# Thrusters_V2_0.net
KiCad netlist of a schematic drawn in Altium Designer
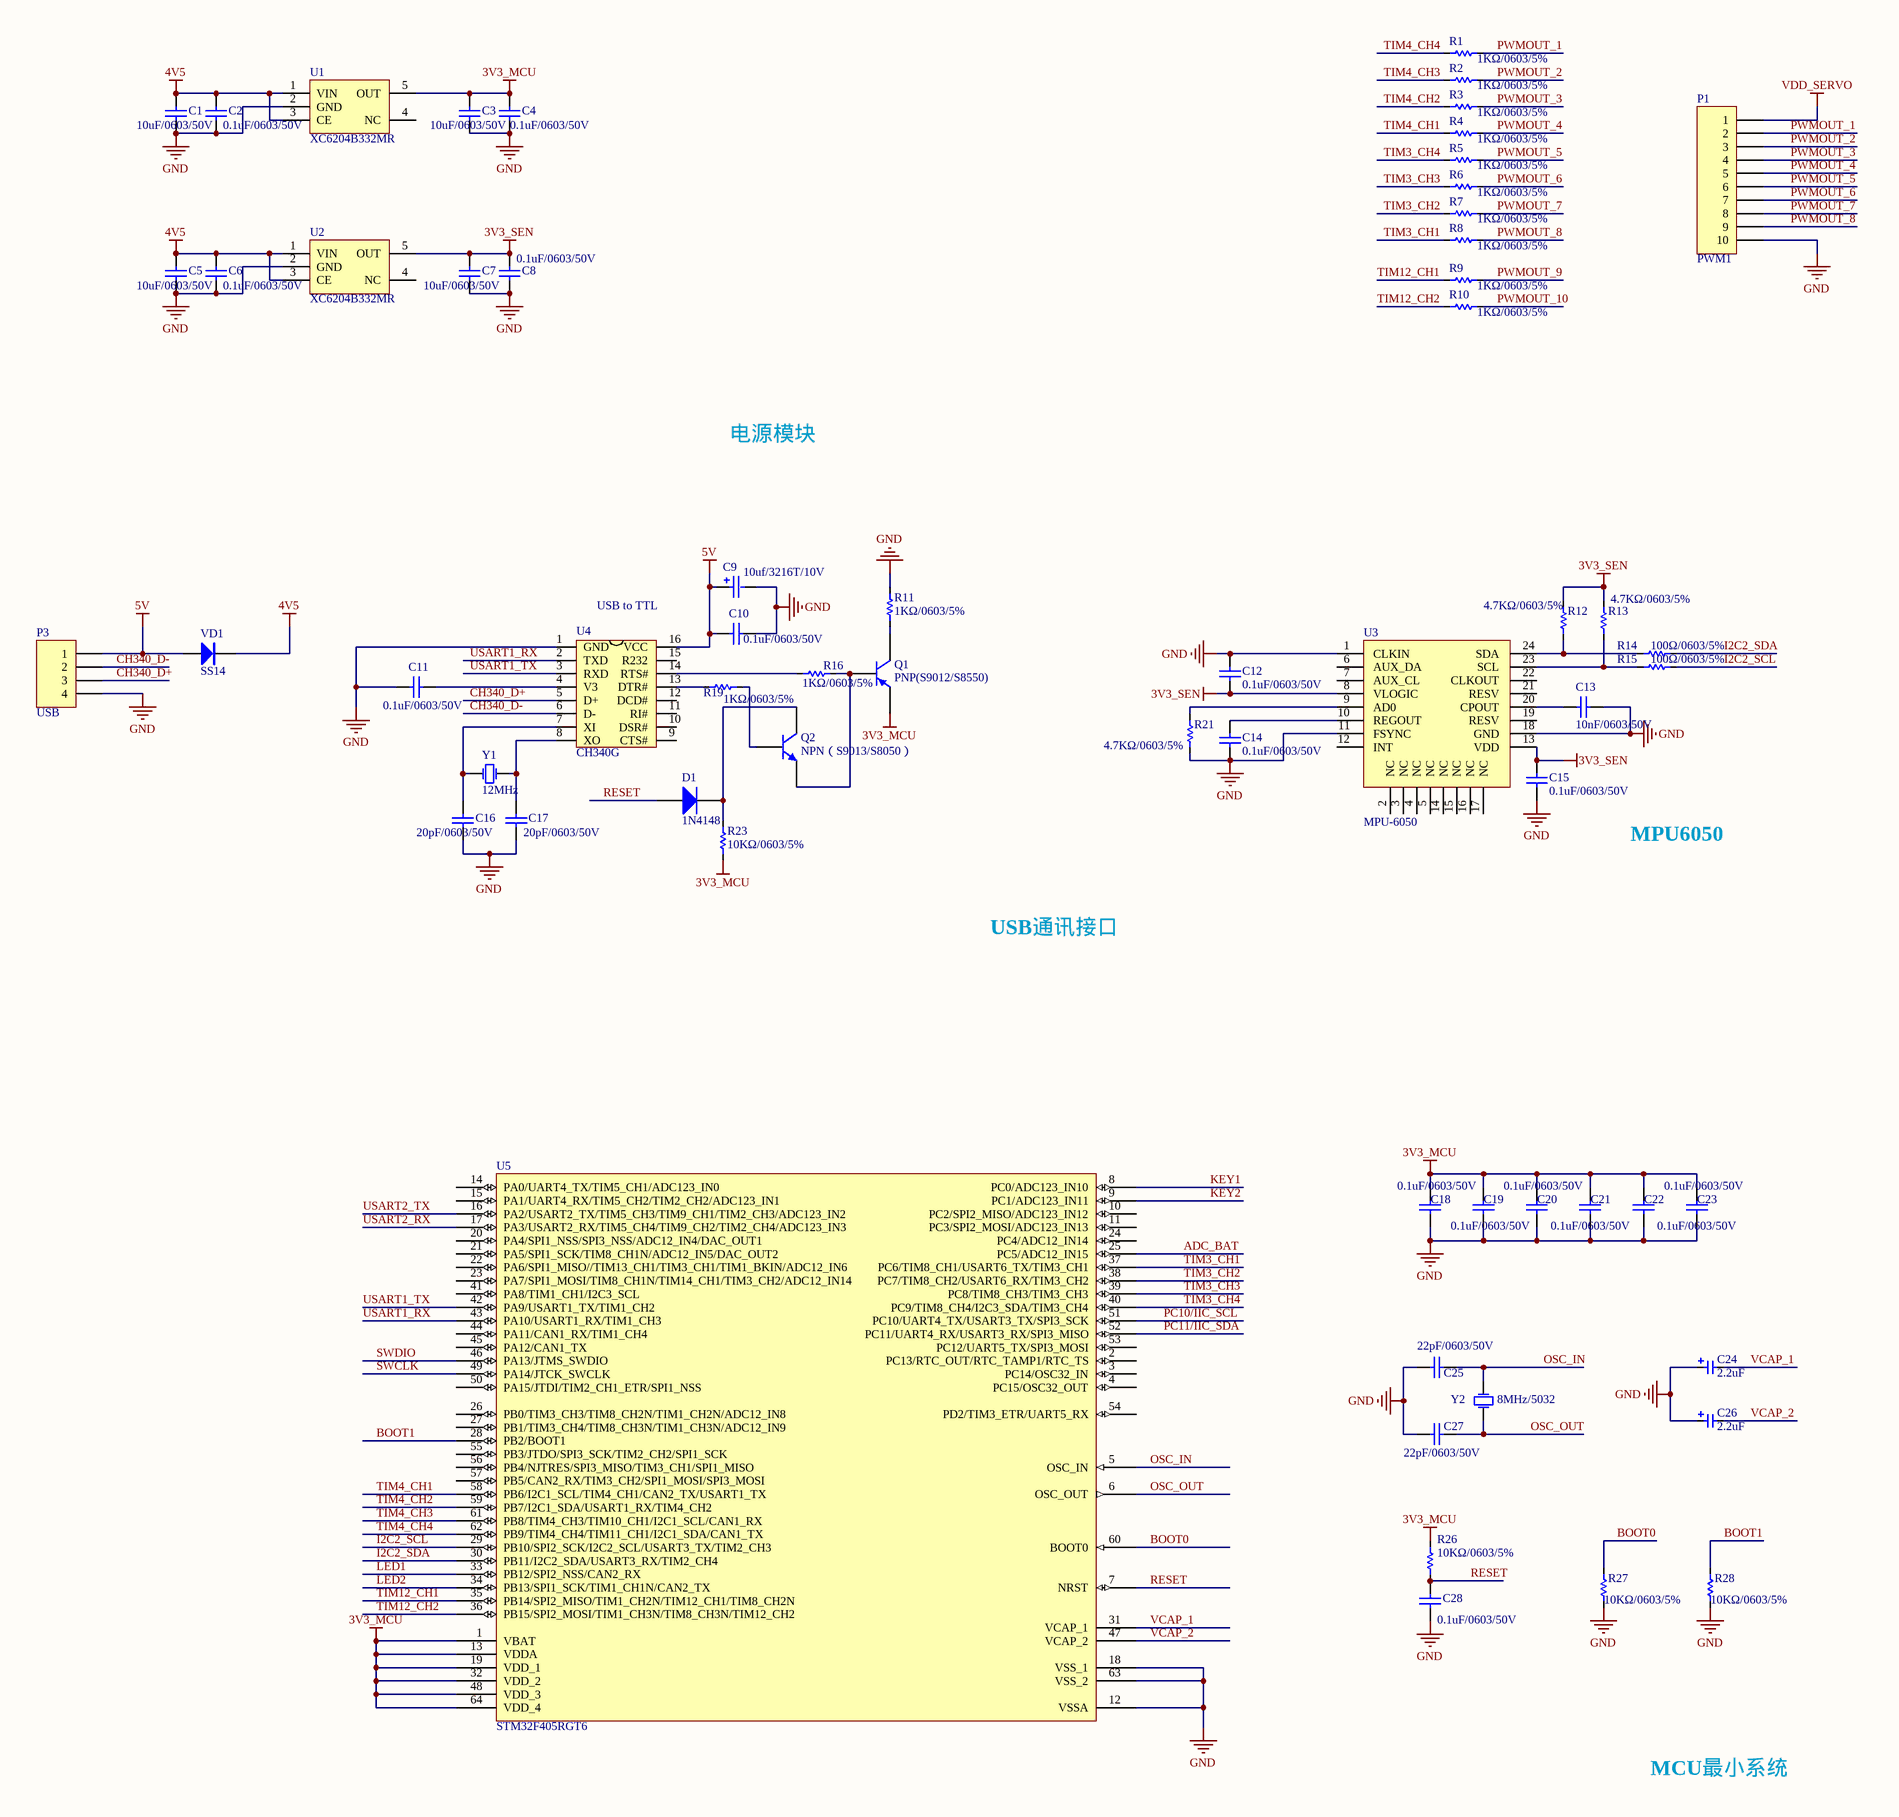
[diagram p0: Thrusters_V2.0.SchDoc, left]
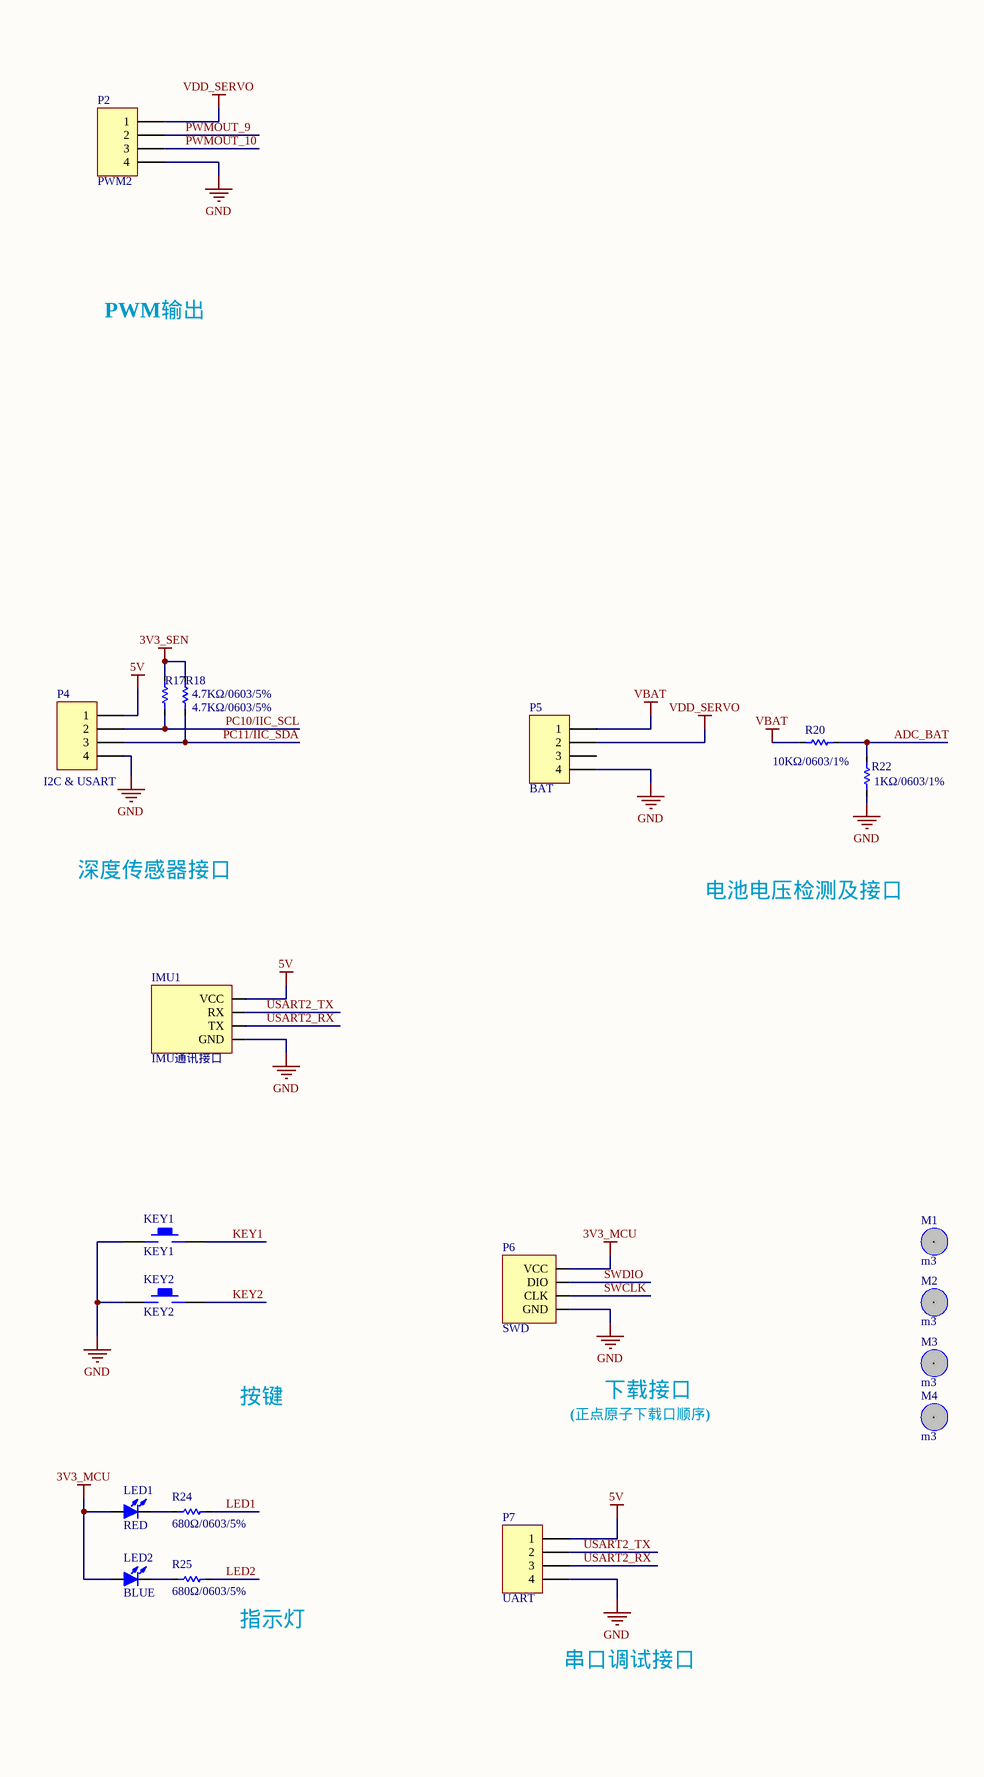
[diagram p1: Thrusters_V2.0.SchDoc, right]

(export (version "E")
  (design (tool "Eeschema 10.0.6"))
  (components
    (comp (ref "C1")
      (value "10uF/0603/50V")
      (footprint "C0805-JLC")
      (description "CAP 0805 0603 0402")
      (libsource (lib "wgcoSchlib") (part "CAP_0805/0603/0402"))
    )
    (comp (ref "C2")
      (value "0.1uF/0603/50V")
      (footprint "C0603-JLC")
      (description "CAP 0805 0603 0402")
      (libsource (lib "wgcoSchlib") (part "CAP_0805/0603/0402"))
    )
    (comp (ref "C3")
      (value "10uF/0603/50V")
      (footprint "C0805-JLC")
      (description "CAP 0805 0603 0402")
      (libsource (lib "wgcoSchlib") (part "CAP_0805/0603/0402"))
    )
    (comp (ref "C4")
      (value "0.1uF/0603/50V")
      (footprint "C0603-JLC")
      (description "CAP 0805 0603 0402")
      (libsource (lib "wgcoSchlib") (part "CAP_0805/0603/0402"))
    )
    (comp (ref "C5")
      (value "10uF/0603/50V")
      (footprint "C0805-JLC")
      (description "CAP 0805 0603 0402")
      (libsource (lib "wgcoSchlib") (part "CAP_0805/0603/0402"))
    )
    (comp (ref "C6")
      (value "0.1uF/0603/50V")
      (footprint "C0603-JLC")
      (description "CAP 0805 0603 0402")
      (libsource (lib "wgcoSchlib") (part "CAP_0805/0603/0402"))
    )
    (comp (ref "C7")
      (value "10uF/0603/50V")
      (footprint "C0805-JLC")
      (description "CAP 0805 0603 0402")
      (libsource (lib "wgcoSchlib") (part "CAP_0805/0603/0402"))
    )
    (comp (ref "C8")
      (value "0.1uF/0603/50V")
      (footprint "C0603-JLC")
      (description "CAP 0805 0603 0402")
      (libsource (lib "wgcoSchlib") (part "CAP_0805/0603/0402"))
    )
    (comp (ref "C9")
      (value "10uf/3216T/10V")
      (footprint "Cap Poll 1(3216T)")
      (description "Polarized Capacitor (Surface Mount)(钽电容)")
      (libsource (lib "wgcoSchlib") (part "Cap Poll"))
    )
    (comp (ref "C10")
      (value "0.1uF/0603/50V")
      (footprint "C0603-JLC")
      (description "CAP 0805 0603 0402")
      (libsource (lib "wgcoSchlib") (part "CAP_0805/0603/0402"))
    )
    (comp (ref "C11")
      (value "0.1uF/0603/50V")
      (footprint "C0603-JLC")
      (description "CAP 0805 0603 0402")
      (libsource (lib "wgcoSchlib") (part "CAP_0805/0603/0402"))
    )
    (comp (ref "C12")
      (value "0.1uF/0603/50V")
      (footprint "C0603-JLC")
      (description "CAP 0805 0603 0402")
      (libsource (lib "wgcoSchlib") (part "CAP_0805/0603/0402"))
    )
    (comp (ref "C13")
      (value "10nF/0603/50V")
      (footprint "C0603-JLC")
      (description "CAP 0805 0603 0402")
      (libsource (lib "wgcoSchlib") (part "CAP_0805/0603/0402"))
    )
    (comp (ref "C14")
      (value "0.1uF/0603/50V")
      (footprint "C0603-JLC")
      (description "CAP 0805 0603 0402")
      (libsource (lib "wgcoSchlib") (part "CAP_0805/0603/0402"))
    )
    (comp (ref "C15")
      (value "0.1uF/0603/50V")
      (footprint "C0603-JLC")
      (description "CAP 0805 0603 0402")
      (libsource (lib "wgcoSchlib") (part "CAP_0805/0603/0402"))
    )
    (comp (ref "C16")
      (value "20pF/0603/50V")
      (footprint "C0603-JLC")
      (description "CAP 0805 0603 0402")
      (libsource (lib "wgcoSchlib") (part "CAP_0805/0603/0402"))
    )
    (comp (ref "C17")
      (value "20pF/0603/50V")
      (footprint "C0603-JLC")
      (description "CAP 0805 0603 0402")
      (libsource (lib "wgcoSchlib") (part "CAP_0805/0603/0402"))
    )
    (comp (ref "C18")
      (value "0.1uF/0603/50V")
      (footprint "C0603-JLC")
      (description "CAP 0805 0603 0402")
      (libsource (lib "wgcoSchlib") (part "CAP_0805/0603/0402"))
    )
    (comp (ref "C19")
      (value "0.1uF/0603/50V")
      (footprint "C0603-JLC")
      (description "CAP 0805 0603 0402")
      (libsource (lib "wgcoSchlib") (part "CAP_0805/0603/0402"))
    )
    (comp (ref "C20")
      (value "0.1uF/0603/50V")
      (footprint "C0603-JLC")
      (description "CAP 0805 0603 0402")
      (libsource (lib "wgcoSchlib") (part "CAP_0805/0603/0402"))
    )
    (comp (ref "C21")
      (value "0.1uF/0603/50V")
      (footprint "C0603-JLC")
      (description "CAP 0805 0603 0402")
      (libsource (lib "wgcoSchlib") (part "CAP_0805/0603/0402"))
    )
    (comp (ref "C22")
      (value "0.1uF/0603/50V")
      (footprint "C0603-JLC")
      (description "CAP 0805 0603 0402")
      (libsource (lib "wgcoSchlib") (part "CAP_0805/0603/0402"))
    )
    (comp (ref "C23")
      (value "0.1uF/0603/50V")
      (footprint "C0603-JLC")
      (description "CAP 0805 0603 0402")
      (libsource (lib "wgcoSchlib") (part "CAP_0805/0603/0402"))
    )
    (comp (ref "C24")
      (value "2.2uF")
      (footprint "0603_C")
      (description "Polarized Capacitor (Surface Mount)(钽电容)")
      (fields (field (name "Comment") "Cap_Tan_0805"))
      (libsource (lib "wgcoSchlib") (part "Cap_Tan_0805"))
    )
    (comp (ref "C25")
      (value "22pF/0603/50V")
      (footprint "C0603-JLC")
      (description "CAP 0805 0603 0402")
      (libsource (lib "wgcoSchlib") (part "CAP_0805/0603/0402"))
    )
    (comp (ref "C26")
      (value "2.2uF")
      (footprint "0603_C")
      (description "Polarized Capacitor (Surface Mount)(钽电容)")
      (fields (field (name "Comment") "Cap_Tan_0805"))
      (libsource (lib "wgcoSchlib") (part "Cap_Tan_0805"))
    )
    (comp (ref "C27")
      (value "22pF/0603/50V")
      (footprint "C0603-JLC")
      (description "CAP 0805 0603 0402")
      (libsource (lib "wgcoSchlib") (part "CAP_0805/0603/0402"))
    )
    (comp (ref "C28")
      (value "0.1uF/0603/50V")
      (footprint "C0603-JLC")
      (description "CAP 0805 0603 0402")
      (libsource (lib "wgcoSchlib") (part "CAP_0805/0603/0402"))
    )
    (comp (ref "D1") (value "1N4148") (footprint "SOD-123F") (libsource (lib "wgcoSchlib") (part "D")))
    (comp (ref "IMU1")
      (value "IMU通讯接口")
      (footprint "ATK-IMU901")
      (description "正点原子ATK-IMU901模块接口")
      (libsource (lib "wgcoSchlib") (part "ATK-IMU901"))
    )
    (comp (ref "KEY1")
      (value "KEY1")
      (footprint "button-3x4x2mm 2 Pad")
      (description "按键")
      (libsource (lib "wgcoSchlib") (part "KEY"))
    )
    (comp (ref "KEY2")
      (value "KEY2")
      (footprint "button-3x4x2mm 2 Pad")
      (description "按键")
      (libsource (lib "wgcoSchlib") (part "KEY"))
    )
    (comp (ref "LED1")
      (value "RED")
      (footprint "LED0603-RED-JLC")
      (description "贴片LED")
      (fields (field (name "版权归属") "源创客"))
      (libsource (lib "wgcoSchlib") (part "LED-SMD"))
    )
    (comp (ref "LED2")
      (value "BLUE")
      (footprint "LED0603-RED-JLC")
      (description "贴片LED")
      (fields (field (name "版权归属") "源创客"))
      (libsource (lib "wgcoSchlib") (part "LED-SMD"))
    )
    (comp (ref "M1")
      (value "m3")
      (footprint "M3固定孔")
      (description "M3固定孔")
      (libsource (lib "wgcoSchlib") (part "M3固定孔"))
    )
    (comp (ref "M2")
      (value "m3")
      (footprint "M3固定孔")
      (description "M3固定孔")
      (libsource (lib "wgcoSchlib") (part "M3固定孔"))
    )
    (comp (ref "M3")
      (value "m3")
      (footprint "M3固定孔")
      (description "M3固定孔")
      (libsource (lib "wgcoSchlib") (part "M3固定孔"))
    )
    (comp (ref "M4")
      (value "m3")
      (footprint "M3固定孔")
      (description "M3固定孔")
      (libsource (lib "wgcoSchlib") (part "M3固定孔"))
    )
    (comp (ref "P1")
      (value "PWM1")
      (footprint "HEADER-GH1.25-10P")
      (description "Header, 8-Pin")
      (libsource (lib "wgcoSchlib") (part "HEADER10"))
    )
    (comp (ref "P2")
      (value "PWM2")
      (footprint "HEADER-GH1.25-4P")
      (description "Header, 4-Pin")
      (libsource (lib "wgcoSchlib") (part "HEADER4"))
    )
    (comp (ref "P3")
      (value "USB")
      (footprint "HEADER-GH1.25-4P")
      (description "Header, 4-Pin")
      (libsource (lib "wgcoSchlib") (part "HEADER4"))
    )
    (comp (ref "P4")
      (value "I2C & USART")
      (footprint "HEADER-GH1.25-4P")
      (description "Header, 4-Pin")
      (libsource (lib "wgcoSchlib") (part "HEADER4"))
    )
    (comp (ref "P5")
      (value "BAT")
      (footprint "HEADER-GH1.25-4P")
      (description "Header, 4-Pin")
      (libsource (lib "wgcoSchlib") (part "HEADER4"))
    )
    (comp (ref "P6")
      (value "SWD")
      (footprint "HEADER-SH1.0-4P-A")
      (description "SWD调试下载接口")
      (libsource (lib "wgcoSchlib") (part "SWD-下载接口"))
    )
    (comp (ref "P7")
      (value "UART")
      (footprint "HEADER-GH1.25-4P")
      (description "Header, 4-Pin")
      (libsource (lib "wgcoSchlib") (part "HEADER4"))
    )
    (comp (ref "Q1")
      (value "PNP(S9012/S8550)")
      (footprint "NPN(S8050/S9103)贴片")
      (description "PNP Bipolar Transistor")
      (libsource (lib "wgcoSchlib") (part "PNP(S9012/S8550)"))
    )
    (comp (ref "Q2")
      (value "NPN（S9013/S8050）")
      (footprint "NPN(S8050/S9103)贴片")
      (description "NPN Bipolar Transistor")
      (libsource (lib "wgcoSchlib") (part "NPN(S9103/S8050)"))
    )
    (comp (ref "R1")
      (value "1KΩ/0603/5%")
      (footprint "R0603-JLC")
      (description "Resistor")
      (fields (field (name "POWER") "1/16W"))
      (libsource (lib "wgcoSchlib") (part "Res"))
    )
    (comp (ref "R2")
      (value "1KΩ/0603/5%")
      (footprint "R0603-JLC")
      (description "Resistor")
      (fields (field (name "POWER") "1/16W"))
      (libsource (lib "wgcoSchlib") (part "Res"))
    )
    (comp (ref "R3")
      (value "1KΩ/0603/5%")
      (footprint "R0603-JLC")
      (description "Resistor")
      (fields (field (name "POWER") "1/16W"))
      (libsource (lib "wgcoSchlib") (part "Res"))
    )
    (comp (ref "R4")
      (value "1KΩ/0603/5%")
      (footprint "R0603-JLC")
      (description "Resistor")
      (fields (field (name "POWER") "1/16W"))
      (libsource (lib "wgcoSchlib") (part "Res"))
    )
    (comp (ref "R5")
      (value "1KΩ/0603/5%")
      (footprint "R0603-JLC")
      (description "Resistor")
      (fields (field (name "POWER") "1/16W"))
      (libsource (lib "wgcoSchlib") (part "Res"))
    )
    (comp (ref "R6")
      (value "1KΩ/0603/5%")
      (footprint "R0603-JLC")
      (description "Resistor")
      (fields (field (name "POWER") "1/16W"))
      (libsource (lib "wgcoSchlib") (part "Res"))
    )
    (comp (ref "R7")
      (value "1KΩ/0603/5%")
      (footprint "R0603-JLC")
      (description "Resistor")
      (fields (field (name "POWER") "1/16W"))
      (libsource (lib "wgcoSchlib") (part "Res"))
    )
    (comp (ref "R8")
      (value "1KΩ/0603/5%")
      (footprint "R0603-JLC")
      (description "Resistor")
      (fields (field (name "POWER") "1/16W"))
      (libsource (lib "wgcoSchlib") (part "Res"))
    )
    (comp (ref "R9")
      (value "1KΩ/0603/5%")
      (footprint "R0603-JLC")
      (description "Resistor")
      (fields (field (name "POWER") "1/16W"))
      (libsource (lib "wgcoSchlib") (part "Res"))
    )
    (comp (ref "R10")
      (value "1KΩ/0603/5%")
      (footprint "R0603-JLC")
      (description "Resistor")
      (fields (field (name "POWER") "1/16W"))
      (libsource (lib "wgcoSchlib") (part "Res"))
    )
    (comp (ref "R11")
      (value "1KΩ/0603/5%")
      (footprint "R0603-JLC")
      (description "Resistor")
      (fields (field (name "POWER") "1/16W"))
      (libsource (lib "wgcoSchlib") (part "Res"))
    )
    (comp (ref "R12")
      (value "4.7KΩ/0603/5%")
      (footprint "R0603-JLC")
      (description "Resistor")
      (fields (field (name "POWER") "1/16W"))
      (libsource (lib "wgcoSchlib") (part "Res"))
    )
    (comp (ref "R13")
      (value "4.7KΩ/0603/5%")
      (footprint "R0603-JLC")
      (description "Resistor")
      (fields (field (name "POWER") "1/16W"))
      (libsource (lib "wgcoSchlib") (part "Res"))
    )
    (comp (ref "R14")
      (value "100Ω/0603/5%")
      (footprint "R0603-JLC")
      (description "Resistor")
      (fields (field (name "POWER") "1/16W"))
      (libsource (lib "wgcoSchlib") (part "Res"))
    )
    (comp (ref "R15")
      (value "100Ω/0603/5%")
      (footprint "R0603-JLC")
      (description "Resistor")
      (fields (field (name "POWER") "1/16W"))
      (libsource (lib "wgcoSchlib") (part "Res"))
    )
    (comp (ref "R16")
      (value "1KΩ/0603/5%")
      (footprint "R0603-JLC")
      (description "Resistor")
      (fields (field (name "POWER") "1/16W"))
      (libsource (lib "wgcoSchlib") (part "Res"))
    )
    (comp (ref "R17")
      (value "4.7KΩ/0603/5%")
      (footprint "R0603-JLC")
      (description "Resistor")
      (fields (field (name "POWER") "1/16W"))
      (libsource (lib "wgcoSchlib") (part "Res"))
    )
    (comp (ref "R18")
      (value "4.7KΩ/0603/5%")
      (footprint "R0603-JLC")
      (description "Resistor")
      (fields (field (name "POWER") "1/16W"))
      (libsource (lib "wgcoSchlib") (part "Res"))
    )
    (comp (ref "R19")
      (value "1KΩ/0603/5%")
      (footprint "R0603-JLC")
      (description "Resistor")
      (fields (field (name "POWER") "1/16W"))
      (libsource (lib "wgcoSchlib") (part "Res"))
    )
    (comp (ref "R20")
      (value "10KΩ/0603/1%")
      (footprint "R0603-JLC")
      (description "Resistor")
      (fields (field (name "POWER") "1/16W"))
      (libsource (lib "wgcoSchlib") (part "Res"))
    )
    (comp (ref "R21")
      (value "4.7KΩ/0603/5%")
      (footprint "R0603-JLC")
      (description "Resistor")
      (fields (field (name "POWER") "1/16W"))
      (libsource (lib "wgcoSchlib") (part "Res"))
    )
    (comp (ref "R22")
      (value "1KΩ/0603/1%")
      (footprint "R0603-JLC")
      (description "Resistor")
      (fields (field (name "POWER") "1/16W"))
      (libsource (lib "wgcoSchlib") (part "Res"))
    )
    (comp (ref "R23")
      (value "10KΩ/0603/5%")
      (footprint "R0603-JLC")
      (description "Resistor")
      (fields (field (name "POWER") "1/16W"))
      (libsource (lib "wgcoSchlib") (part "Res"))
    )
    (comp (ref "R24")
      (value "680Ω/0603/5%")
      (footprint "R0603-JLC")
      (description "Resistor")
      (fields (field (name "POWER") "1/16W"))
      (libsource (lib "wgcoSchlib") (part "Res"))
    )
    (comp (ref "R25")
      (value "680Ω/0603/5%")
      (footprint "R0603-JLC")
      (description "Resistor")
      (fields (field (name "POWER") "1/16W"))
      (libsource (lib "wgcoSchlib") (part "Res"))
    )
    (comp (ref "R26")
      (value "10KΩ/0603/5%")
      (footprint "R0603-JLC")
      (description "Resistor")
      (fields (field (name "POWER") "1/16W"))
      (libsource (lib "wgcoSchlib") (part "Res"))
    )
    (comp (ref "R27")
      (value "10KΩ/0603/5%")
      (footprint "R0603-JLC")
      (description "Resistor")
      (fields (field (name "POWER") "1/16W"))
      (libsource (lib "wgcoSchlib") (part "Res"))
    )
    (comp (ref "R28")
      (value "10KΩ/0603/5%")
      (footprint "R0603-JLC")
      (description "Resistor")
      (fields (field (name "POWER") "1/16W"))
      (libsource (lib "wgcoSchlib") (part "Res"))
    )
    (comp (ref "U1")
      (value "XC6204B332MR")
      (footprint "XC6204B332MR")
      (description "LDO")
      (fields (field (name "版权归属") "源创客"))
      (libsource (lib "wgcoSchlib") (part "LDO XC6204"))
    )
    (comp (ref "U2")
      (value "XC6204B332MR")
      (footprint "XC6204B332MR")
      (description "LDO")
      (fields (field (name "版权归属") "源创客"))
      (libsource (lib "wgcoSchlib") (part "LDO XC6204"))
    )
    (comp (ref "U3")
      (value "MPU-6050")
      (footprint "MPU6050-JLC")
      (libsource (lib "wgcoSchlib") (part "MPU-6050"))
    )
    (comp (ref "U4")
      (value "CH340G")
      (footprint "SOP16M")
      (description "USB2UART")
      (libsource (lib "wgcoSchlib") (part "CH340G"))
    )
    (comp (ref "U5")
      (value "STM32F405RGT6")
      (footprint "STM32_LQFP64")
      (description "STM32 ARM-based 32-bit MCU with 1024 Kbytes of Flash memory, 64-pin LQFP, Industrial Temperature")
      (libsource (lib "wgcoSchlib") (part "STM32F405RGT6"))
    )
    (comp (ref "VD1")
      (value "SS14")
      (footprint "SOD-123")
      (description "肖特基二极管")
      (fields (field (name "版权归属") "源创客"))
      (libsource (lib "wgcoSchlib") (part "SS14"))
    )
    (comp (ref "Y1")
      (value "12MHz")
      (footprint "XT_5032_2P")
      (description "Crystal Oscillator")
      (fields (field (name "Comment") "12MHz/5032"))
      (libsource (lib "wgcoSchlib") (part "XTAL"))
    )
    (comp (ref "Y2")
      (value "8MHz/5032")
      (footprint "XT_5032_2P")
      (description "Crystal Oscillator")
      (libsource (lib "wgcoSchlib") (part "XTAL"))
    )
  )
  (nets
    (net (code "1") (name "/ADC_BAT") (class "Default")
      (node (ref "R20") (pin "2") (pinfunction "2_2") (pintype "passive"))
      (node (ref "R22") (pin "1") (pinfunction "1_1") (pintype "passive"))
      (node (ref "U5") (pin "25") (pinfunction "PC5/ADC12_IN15_25") (pintype "bidirectional"))
    )
    (net (code "2") (name "/BOOT0") (class "Default")
      (node (ref "R27") (pin "2") (pinfunction "2_2") (pintype "passive"))
      (node (ref "U5") (pin "60") (pinfunction "BOOT0_60") (pintype "input"))
    )
    (net (code "3") (name "/BOOT1") (class "Default")
      (node (ref "R28") (pin "2") (pinfunction "2_2") (pintype "passive"))
      (node (ref "U5") (pin "28") (pinfunction "PB2/BOOT1_28") (pintype "bidirectional"))
    )
    (net (code "4") (name "/CH340_D+") (class "Default")
      (node (ref "P3") (pin "3") (pinfunction "3_3") (pintype "passive"))
      (node (ref "U4") (pin "5") (pinfunction "D+_5") (pintype "passive"))
    )
    (net (code "5") (name "/CH340_D-") (class "Default")
      (node (ref "P3") (pin "2") (pinfunction "2_2") (pintype "passive"))
      (node (ref "U4") (pin "6") (pinfunction "D-_6") (pintype "passive"))
    )
    (net (code "6") (name "/I2C2_SCL") (class "Default")
      (node (ref "R15") (pin "2") (pinfunction "2_2") (pintype "passive"))
      (node (ref "U5") (pin "29") (pinfunction "PB10/SPI2_SCK/I2C2_SCL/USART3_TX/TIM2_CH3_29") (pintype "bidirectional"))
    )
    (net (code "7") (name "/I2C2_SDA") (class "Default")
      (node (ref "R14") (pin "2") (pinfunction "2_2") (pintype "passive"))
      (node (ref "U5") (pin "30") (pinfunction "PB11/I2C2_SDA/USART3_RX/TIM2_CH4_30") (pintype "bidirectional"))
    )
    (net (code "8") (name "/KEY1") (class "Default")
      (node (ref "KEY1") (pin "2") (pinfunction "2_2") (pintype "passive"))
      (node (ref "U5") (pin "8") (pinfunction "PC0/ADC123_IN10_8") (pintype "bidirectional"))
    )
    (net (code "9") (name "/KEY2") (class "Default")
      (node (ref "KEY2") (pin "2") (pinfunction "2_2") (pintype "passive"))
      (node (ref "U5") (pin "9") (pinfunction "PC1/ADC123_IN11_9") (pintype "bidirectional"))
    )
    (net (code "10") (name "/LED1") (class "Default")
      (node (ref "R24") (pin "1") (pinfunction "1_1") (pintype "passive"))
      (node (ref "U5") (pin "33") (pinfunction "PB12/SPI2_NSS/CAN2_RX_33") (pintype "bidirectional"))
    )
    (net (code "11") (name "/LED2") (class "Default")
      (node (ref "R25") (pin "1") (pinfunction "1_1") (pintype "passive"))
      (node (ref "U5") (pin "34") (pinfunction "PB13/SPI1_SCK/TIM1_CH1N/CAN2_TX_34") (pintype "bidirectional"))
    )
    (net (code "12") (name "/OSC_IN") (class "Default")
      (node (ref "C25") (pin "2") (pinfunction "2_2") (pintype "passive"))
      (node (ref "U5") (pin "5") (pinfunction "OSC_IN_5") (pintype "input"))
      (node (ref "Y2") (pin "2") (pinfunction "OSC2_2") (pintype "passive"))
    )
    (net (code "13") (name "/OSC_OUT") (class "Default")
      (node (ref "C27") (pin "2") (pinfunction "2_2") (pintype "passive"))
      (node (ref "U5") (pin "6") (pinfunction "OSC_OUT_6") (pintype "output"))
      (node (ref "Y2") (pin "1") (pinfunction "OSC1_1") (pintype "passive"))
    )
    (net (code "14") (name "/PC10{slash}IIC_SCL") (class "Default")
      (node (ref "P4") (pin "2") (pinfunction "2_2") (pintype "passive"))
      (node (ref "R17") (pin "2") (pinfunction "2_2") (pintype "passive"))
      (node (ref "U5") (pin "51") (pinfunction "PC10/UART4_TX/USART3_TX/SPI3_SCK_51") (pintype "bidirectional"))
    )
    (net (code "15") (name "/PC11{slash}IIC_SDA") (class "Default")
      (node (ref "P4") (pin "3") (pinfunction "3_3") (pintype "passive"))
      (node (ref "R18") (pin "2") (pinfunction "2_2") (pintype "passive"))
      (node (ref "U5") (pin "52") (pinfunction "PC11/UART4_RX/USART3_RX/SPI3_MISO_52") (pintype "bidirectional"))
    )
    (net (code "16") (name "/PWMOUT_1") (class "Default")
      (node (ref "P1") (pin "2") (pinfunction "2_2") (pintype "passive"))
      (node (ref "R1") (pin "1") (pinfunction "1_1") (pintype "passive"))
    )
    (net (code "17") (name "/PWMOUT_2") (class "Default")
      (node (ref "P1") (pin "3") (pinfunction "3_3") (pintype "passive"))
      (node (ref "R2") (pin "1") (pinfunction "1_1") (pintype "passive"))
    )
    (net (code "18") (name "/PWMOUT_3") (class "Default")
      (node (ref "P1") (pin "4") (pinfunction "4_4") (pintype "passive"))
      (node (ref "R3") (pin "1") (pinfunction "1_1") (pintype "passive"))
    )
    (net (code "19") (name "/PWMOUT_4") (class "Default")
      (node (ref "P1") (pin "5") (pinfunction "5_5") (pintype "passive"))
      (node (ref "R4") (pin "1") (pinfunction "1_1") (pintype "passive"))
    )
    (net (code "20") (name "/PWMOUT_5") (class "Default")
      (node (ref "P1") (pin "6") (pinfunction "6_6") (pintype "passive"))
      (node (ref "R5") (pin "1") (pinfunction "1_1") (pintype "passive"))
    )
    (net (code "21") (name "/PWMOUT_6") (class "Default")
      (node (ref "P1") (pin "7") (pinfunction "7_7") (pintype "passive"))
      (node (ref "R6") (pin "1") (pinfunction "1_1") (pintype "passive"))
    )
    (net (code "22") (name "/PWMOUT_7") (class "Default")
      (node (ref "P1") (pin "8") (pinfunction "8_8") (pintype "passive"))
      (node (ref "R7") (pin "1") (pinfunction "1_1") (pintype "passive"))
    )
    (net (code "23") (name "/PWMOUT_8") (class "Default")
      (node (ref "P1") (pin "9") (pinfunction "9_9") (pintype "passive"))
      (node (ref "R8") (pin "1") (pinfunction "1_1") (pintype "passive"))
    )
    (net (code "24") (name "/PWMOUT_9") (class "Default")
      (node (ref "P2") (pin "2") (pinfunction "2_2") (pintype "passive"))
      (node (ref "R9") (pin "1") (pinfunction "1_1") (pintype "passive"))
    )
    (net (code "25") (name "/PWMOUT_10") (class "Default")
      (node (ref "P2") (pin "3") (pinfunction "3_3") (pintype "passive"))
      (node (ref "R10") (pin "1") (pinfunction "1_1") (pintype "passive"))
    )
    (net (code "26") (name "/RESET") (class "Default")
      (node (ref "C28") (pin "1") (pinfunction "1_1") (pintype "passive"))
      (node (ref "D1") (pin "1") (pinfunction "A_1") (pintype "passive"))
      (node (ref "R26") (pin "1") (pinfunction "1_1") (pintype "passive"))
      (node (ref "U5") (pin "7") (pinfunction "NRST_7") (pintype "bidirectional"))
    )
    (net (code "27") (name "/SWCLK") (class "Default")
      (node (ref "P6") (pin "3") (pinfunction "CLK_3") (pintype "passive"))
      (node (ref "U5") (pin "49") (pinfunction "PA14/JTCK_SWCLK_49") (pintype "bidirectional"))
    )
    (net (code "28") (name "/SWDIO") (class "Default")
      (node (ref "P6") (pin "2") (pinfunction "DIO_2") (pintype "passive"))
      (node (ref "U5") (pin "46") (pinfunction "PA13/JTMS_SWDIO_46") (pintype "bidirectional"))
    )
    (net (code "29") (name "/TIM3_CH1") (class "Default")
      (node (ref "R8") (pin "2") (pinfunction "2_2") (pintype "passive"))
      (node (ref "U5") (pin "37") (pinfunction "PC6/TIM8_CH1/USART6_TX/TIM3_CH1_37") (pintype "bidirectional"))
    )
    (net (code "30") (name "/TIM3_CH2") (class "Default")
      (node (ref "R7") (pin "2") (pinfunction "2_2") (pintype "passive"))
      (node (ref "U5") (pin "38") (pinfunction "PC7/TIM8_CH2/USART6_RX/TIM3_CH2_38") (pintype "bidirectional"))
    )
    (net (code "31") (name "/TIM3_CH3") (class "Default")
      (node (ref "R6") (pin "2") (pinfunction "2_2") (pintype "passive"))
      (node (ref "U5") (pin "39") (pinfunction "PC8/TIM8_CH3/TIM3_CH3_39") (pintype "bidirectional"))
    )
    (net (code "32") (name "/TIM3_CH4") (class "Default")
      (node (ref "R5") (pin "2") (pinfunction "2_2") (pintype "passive"))
      (node (ref "U5") (pin "40") (pinfunction "PC9/TIM8_CH4/I2C3_SDA/TIM3_CH4_40") (pintype "bidirectional"))
    )
    (net (code "33") (name "/TIM4_CH1") (class "Default")
      (node (ref "R4") (pin "2") (pinfunction "2_2") (pintype "passive"))
      (node (ref "U5") (pin "58") (pinfunction "PB6/I2C1_SCL/TIM4_CH1/CAN2_TX/USART1_TX_58") (pintype "bidirectional"))
    )
    (net (code "34") (name "/TIM4_CH2") (class "Default")
      (node (ref "R3") (pin "2") (pinfunction "2_2") (pintype "passive"))
      (node (ref "U5") (pin "59") (pinfunction "PB7/I2C1_SDA/USART1_RX/TIM4_CH2_59") (pintype "bidirectional"))
    )
    (net (code "35") (name "/TIM4_CH3") (class "Default")
      (node (ref "R2") (pin "2") (pinfunction "2_2") (pintype "passive"))
      (node (ref "U5") (pin "61") (pinfunction "PB8/TIM4_CH3/TIM10_CH1/I2C1_SCL/CAN1_RX_61") (pintype "bidirectional"))
    )
    (net (code "36") (name "/TIM4_CH4") (class "Default")
      (node (ref "R1") (pin "2") (pinfunction "2_2") (pintype "passive"))
      (node (ref "U5") (pin "62") (pinfunction "PB9/TIM4_CH4/TIM11_CH1/I2C1_SDA/CAN1_TX_62") (pintype "bidirectional"))
    )
    (net (code "37") (name "/TIM12_CH1") (class "Default")
      (node (ref "R9") (pin "2") (pinfunction "2_2") (pintype "passive"))
      (node (ref "U5") (pin "35") (pinfunction "PB14/SPI2_MISO/TIM1_CH2N/TIM12_CH1/TIM8_CH2N_35") (pintype "bidirectional"))
    )
    (net (code "38") (name "/TIM12_CH2") (class "Default")
      (node (ref "R10") (pin "2") (pinfunction "2_2") (pintype "passive"))
      (node (ref "U5") (pin "36") (pinfunction "PB15/SPI2_MOSI/TIM1_CH3N/TIM8_CH3N/TIM12_CH2_36") (pintype "bidirectional"))
    )
    (net (code "39") (name "/USART1_RX") (class "Default")
      (node (ref "U4") (pin "2") (pinfunction "TXD_2") (pintype "passive"))
      (node (ref "U5") (pin "43") (pinfunction "PA10/USART1_RX/TIM1_CH3_43") (pintype "bidirectional"))
    )
    (net (code "40") (name "/USART1_TX") (class "Default")
      (node (ref "U4") (pin "3") (pinfunction "RXD_3") (pintype "passive"))
      (node (ref "U5") (pin "42") (pinfunction "PA9/USART1_TX/TIM1_CH2_42") (pintype "bidirectional"))
    )
    (net (code "41") (name "/USART2_RX") (class "Default")
      (node (ref "IMU1") (pin "4") (pinfunction "TX_4") (pintype "passive"))
      (node (ref "P7") (pin "3") (pinfunction "3_3") (pintype "passive"))
      (node (ref "U5") (pin "17") (pinfunction "PA3/USART2_RX/TIM5_CH4/TIM9_CH2/TIM2_CH4/ADC123_IN3_17") (pintype "bidirectional"))
    )
    (net (code "42") (name "/USART2_TX") (class "Default")
      (node (ref "IMU1") (pin "3") (pinfunction "RX_3") (pintype "passive"))
      (node (ref "P7") (pin "2") (pinfunction "2_2") (pintype "passive"))
      (node (ref "U5") (pin "16") (pinfunction "PA2/USART2_TX/TIM5_CH3/TIM9_CH1/TIM2_CH3/ADC123_IN2_16") (pintype "bidirectional"))
    )
    (net (code "43") (name "/VCAP_1") (class "Default")
      (node (ref "C24") (pin "2") (pinfunction "2_2") (pintype "passive"))
      (node (ref "U5") (pin "31") (pinfunction "VCAP_1_31") (pintype "power_in"))
    )
    (net (code "44") (name "/VCAP_2") (class "Default")
      (node (ref "C26") (pin "2") (pinfunction "2_2") (pintype "passive"))
      (node (ref "U5") (pin "47") (pinfunction "VCAP_2_47") (pintype "power_in"))
    )
    (net (code "45") (name "3V3_MCU") (class "Default")
      (node (ref "C18") (pin "1") (pinfunction "1_1") (pintype "passive"))
      (node (ref "C19") (pin "1") (pinfunction "1_1") (pintype "passive"))
      (node (ref "C20") (pin "1") (pinfunction "1_1") (pintype "passive"))
      (node (ref "C21") (pin "1") (pinfunction "1_1") (pintype "passive"))
      (node (ref "C22") (pin "1") (pinfunction "1_1") (pintype "passive"))
      (node (ref "C23") (pin "1") (pinfunction "1_1") (pintype "passive"))
      (node (ref "C3") (pin "2") (pinfunction "2_2") (pintype "passive"))
      (node (ref "C4") (pin "1") (pinfunction "1_1") (pintype "passive"))
      (node (ref "LED1") (pin "1") (pinfunction "A_1") (pintype "passive"))
      (node (ref "LED2") (pin "1") (pinfunction "A_1") (pintype "passive"))
      (node (ref "P6") (pin "1") (pinfunction "VCC_1") (pintype "passive"))
      (node (ref "Q1") (pin "E") (pinfunction "E_E") (pintype "passive"))
      (node (ref "R23") (pin "2") (pinfunction "2_2") (pintype "passive"))
      (node (ref "R26") (pin "2") (pinfunction "2_2") (pintype "passive"))
      (node (ref "U1") (pin "5") (pinfunction "OUT_5") (pintype "passive"))
      (node (ref "U5") (pin "1") (pinfunction "VBAT_1") (pintype "power_in"))
      (node (ref "U5") (pin "13") (pinfunction "VDDA_13") (pintype "power_in"))
      (node (ref "U5") (pin "19") (pinfunction "VDD_1_19") (pintype "power_in"))
      (node (ref "U5") (pin "32") (pinfunction "VDD_2_32") (pintype "power_in"))
      (node (ref "U5") (pin "48") (pinfunction "VDD_3_48") (pintype "power_in"))
      (node (ref "U5") (pin "64") (pinfunction "VDD_4_64") (pintype "power_in"))
    )
    (net (code "46") (name "3V3_SEN") (class "Default")
      (node (ref "C12") (pin "1") (pinfunction "1_1") (pintype "passive"))
      (node (ref "C15") (pin "2") (pinfunction "2_2") (pintype "passive"))
      (node (ref "C7") (pin "2") (pinfunction "2_2") (pintype "passive"))
      (node (ref "C8") (pin "1") (pinfunction "1_1") (pintype "passive"))
      (node (ref "R12") (pin "1") (pinfunction "1_1") (pintype "passive"))
      (node (ref "R13") (pin "1") (pinfunction "1_1") (pintype "passive"))
      (node (ref "R17") (pin "1") (pinfunction "1_1") (pintype "passive"))
      (node (ref "R18") (pin "1") (pinfunction "1_1") (pintype "passive"))
      (node (ref "U2") (pin "5") (pinfunction "OUT_5") (pintype "passive"))
      (node (ref "U3") (pin "13") (pinfunction "VDD_13") (pintype "passive"))
      (node (ref "U3") (pin "8") (pinfunction "VLOGIC_8") (pintype "passive"))
    )
    (net (code "47") (name "4V5") (class "Default")
      (node (ref "C1") (pin "2") (pinfunction "2_2") (pintype "passive"))
      (node (ref "C2") (pin "1") (pinfunction "1_1") (pintype "passive"))
      (node (ref "C5") (pin "2") (pinfunction "2_2") (pintype "passive"))
      (node (ref "C6") (pin "1") (pinfunction "1_1") (pintype "passive"))
      (node (ref "U1") (pin "1") (pinfunction "VIN_1") (pintype "passive"))
      (node (ref "U1") (pin "3") (pinfunction "CE_3") (pintype "passive"))
      (node (ref "U2") (pin "1") (pinfunction "VIN_1") (pintype "passive"))
      (node (ref "U2") (pin "3") (pinfunction "CE_3") (pintype "passive"))
      (node (ref "VD1") (pin "2") (pinfunction "K_2") (pintype "passive"))
    )
    (net (code "48") (name "5V") (class "Default")
      (node (ref "C10") (pin "1") (pinfunction "1_1") (pintype "passive"))
      (node (ref "C9") (pin "1") (pinfunction "1_1") (pintype "passive"))
      (node (ref "IMU1") (pin "2") (pinfunction "VCC_2") (pintype "passive"))
      (node (ref "P3") (pin "1") (pinfunction "1_1") (pintype "passive"))
      (node (ref "P4") (pin "1") (pinfunction "1_1") (pintype "passive"))
      (node (ref "P7") (pin "1") (pinfunction "1_1") (pintype "passive"))
      (node (ref "U4") (pin "16") (pinfunction "VCC_16") (pintype "passive"))
      (node (ref "VD1") (pin "1") (pinfunction "A_1") (pintype "passive"))
    )
    (net (code "49") (name "GND") (class "Default")
      (node (ref "C1") (pin "1") (pinfunction "1_1") (pintype "passive"))
      (node (ref "C10") (pin "2") (pinfunction "2_2") (pintype "passive"))
      (node (ref "C11") (pin "2") (pinfunction "2_2") (pintype "passive"))
      (node (ref "C12") (pin "2") (pinfunction "2_2") (pintype "passive"))
      (node (ref "C13") (pin "1") (pinfunction "1_1") (pintype "passive"))
      (node (ref "C14") (pin "1") (pinfunction "1_1") (pintype "passive"))
      (node (ref "C15") (pin "1") (pinfunction "1_1") (pintype "passive"))
      (node (ref "C16") (pin "1") (pinfunction "1_1") (pintype "passive"))
      (node (ref "C17") (pin "1") (pinfunction "1_1") (pintype "passive"))
      (node (ref "C18") (pin "2") (pinfunction "2_2") (pintype "passive"))
      (node (ref "C19") (pin "2") (pinfunction "2_2") (pintype "passive"))
      (node (ref "C2") (pin "2") (pinfunction "2_2") (pintype "passive"))
      (node (ref "C20") (pin "2") (pinfunction "2_2") (pintype "passive"))
      (node (ref "C21") (pin "2") (pinfunction "2_2") (pintype "passive"))
      (node (ref "C22") (pin "2") (pinfunction "2_2") (pintype "passive"))
      (node (ref "C23") (pin "2") (pinfunction "2_2") (pintype "passive"))
      (node (ref "C24") (pin "1") (pinfunction "1_1") (pintype "passive"))
      (node (ref "C25") (pin "1") (pinfunction "1_1") (pintype "passive"))
      (node (ref "C26") (pin "1") (pinfunction "1_1") (pintype "passive"))
      (node (ref "C27") (pin "1") (pinfunction "1_1") (pintype "passive"))
      (node (ref "C28") (pin "2") (pinfunction "2_2") (pintype "passive"))
      (node (ref "C3") (pin "1") (pinfunction "1_1") (pintype "passive"))
      (node (ref "C4") (pin "2") (pinfunction "2_2") (pintype "passive"))
      (node (ref "C5") (pin "1") (pinfunction "1_1") (pintype "passive"))
      (node (ref "C6") (pin "2") (pinfunction "2_2") (pintype "passive"))
      (node (ref "C7") (pin "1") (pinfunction "1_1") (pintype "passive"))
      (node (ref "C8") (pin "2") (pinfunction "2_2") (pintype "passive"))
      (node (ref "C9") (pin "2") (pinfunction "2_2") (pintype "passive"))
      (node (ref "IMU1") (pin "5") (pinfunction "GND_5") (pintype "passive"))
      (node (ref "KEY1") (pin "1") (pinfunction "1_1") (pintype "passive"))
      (node (ref "KEY2") (pin "1") (pinfunction "1_1") (pintype "passive"))
      (node (ref "P1") (pin "10") (pinfunction "10_10") (pintype "passive"))
      (node (ref "P2") (pin "4") (pinfunction "4_4") (pintype "passive"))
      (node (ref "P3") (pin "4") (pinfunction "4_4") (pintype "passive"))
      (node (ref "P4") (pin "4") (pinfunction "4_4") (pintype "passive"))
      (node (ref "P5") (pin "4") (pinfunction "4_4") (pintype "passive"))
      (node (ref "P6") (pin "4") (pinfunction "GND_4") (pintype "passive"))
      (node (ref "P7") (pin "4") (pinfunction "4_4") (pintype "passive"))
      (node (ref "R11") (pin "1") (pinfunction "1_1") (pintype "passive"))
      (node (ref "R21") (pin "2") (pinfunction "2_2") (pintype "passive"))
      (node (ref "R22") (pin "2") (pinfunction "2_2") (pintype "passive"))
      (node (ref "R27") (pin "1") (pinfunction "1_1") (pintype "passive"))
      (node (ref "R28") (pin "1") (pinfunction "1_1") (pintype "passive"))
      (node (ref "U1") (pin "2") (pinfunction "GND_2") (pintype "passive"))
      (node (ref "U2") (pin "2") (pinfunction "GND_2") (pintype "passive"))
      (node (ref "U3") (pin "1") (pinfunction "CLKIN_1") (pintype "passive"))
      (node (ref "U3") (pin "11") (pinfunction "FSYNC_11") (pintype "passive"))
      (node (ref "U3") (pin "18") (pinfunction "GND_18") (pintype "passive"))
      (node (ref "U4") (pin "1") (pinfunction "GND_1") (pintype "passive"))
      (node (ref "U5") (pin "12") (pinfunction "VSSA_12") (pintype "power_in"))
      (node (ref "U5") (pin "18") (pinfunction "VSS_1_18") (pintype "power_in"))
      (node (ref "U5") (pin "63") (pinfunction "VSS_2_63") (pintype "power_in"))
    )
    (net (code "50") (name "Net-(D1-K)") (class "Default")
      (node (ref "D1") (pin "2") (pinfunction "K_2") (pintype "passive"))
      (node (ref "Q2") (pin "C") (pinfunction "C_C") (pintype "passive"))
      (node (ref "R23") (pin "1") (pinfunction "1_1") (pintype "passive"))
    )
    (net (code "51") (name "Net-(LED1-K)") (class "Default")
      (node (ref "LED1") (pin "2") (pinfunction "K_2") (pintype "passive"))
      (node (ref "R24") (pin "2") (pinfunction "2_2") (pintype "passive"))
    )
    (net (code "52") (name "Net-(LED2-K)") (class "Default")
      (node (ref "LED2") (pin "2") (pinfunction "K_2") (pintype "passive"))
      (node (ref "R25") (pin "2") (pinfunction "2_2") (pintype "passive"))
    )
    (net (code "53") (name "Net-(Q1-PadB)") (class "Default")
      (node (ref "Q1") (pin "B") (pinfunction "B_B") (pintype "passive"))
      (node (ref "Q2") (pin "E") (pinfunction "E_E") (pintype "passive"))
      (node (ref "R16") (pin "1") (pinfunction "1_1") (pintype "passive"))
    )
    (net (code "54") (name "Net-(Q1-PadC)") (class "Default")
      (node (ref "Q1") (pin "C") (pinfunction "C_C") (pintype "passive"))
      (node (ref "R11") (pin "2") (pinfunction "2_2") (pintype "passive"))
    )
    (net (code "55") (name "Net-(Q2-PadB)") (class "Default")
      (node (ref "Q2") (pin "B") (pinfunction "B_B") (pintype "passive"))
      (node (ref "R19") (pin "1") (pinfunction "1_1") (pintype "passive"))
    )
    (net (code "56") (name "Net-(U3-AD0)") (class "Default")
      (node (ref "R21") (pin "1") (pinfunction "1_1") (pintype "passive"))
      (node (ref "U3") (pin "9") (pinfunction "AD0_9") (pintype "passive"))
    )
    (net (code "57") (name "Net-(U3-CPOUT)") (class "Default")
      (node (ref "C13") (pin "2") (pinfunction "2_2") (pintype "passive"))
      (node (ref "U3") (pin "20") (pinfunction "CPOUT_20") (pintype "passive"))
    )
    (net (code "58") (name "Net-(U3-REGOUT)") (class "Default")
      (node (ref "C14") (pin "2") (pinfunction "2_2") (pintype "passive"))
      (node (ref "U3") (pin "10") (pinfunction "REGOUT_10") (pintype "passive"))
    )
    (net (code "59") (name "Net-(U3-SCL)") (class "Default")
      (node (ref "R13") (pin "2") (pinfunction "2_2") (pintype "passive"))
      (node (ref "R15") (pin "1") (pinfunction "1_1") (pintype "passive"))
      (node (ref "U3") (pin "23") (pinfunction "SCL_23") (pintype "passive"))
    )
    (net (code "60") (name "Net-(U3-SDA)") (class "Default")
      (node (ref "R12") (pin "2") (pinfunction "2_2") (pintype "passive"))
      (node (ref "R14") (pin "1") (pinfunction "1_1") (pintype "passive"))
      (node (ref "U3") (pin "24") (pinfunction "SDA_24") (pintype "passive"))
    )
    (net (code "61") (name "Net-(U4-DTR#)") (class "Default")
      (node (ref "R19") (pin "2") (pinfunction "2_2") (pintype "passive"))
      (node (ref "U4") (pin "13") (pinfunction "DTR#_13") (pintype "passive"))
    )
    (net (code "62") (name "Net-(U4-RTS#)") (class "Default")
      (node (ref "R16") (pin "2") (pinfunction "2_2") (pintype "passive"))
      (node (ref "U4") (pin "14") (pinfunction "RTS#_14") (pintype "passive"))
    )
    (net (code "63") (name "Net-(U4-V3)") (class "Default")
      (node (ref "C11") (pin "1") (pinfunction "1_1") (pintype "passive"))
      (node (ref "U4") (pin "4") (pinfunction "V3_4") (pintype "passive"))
    )
    (net (code "64") (name "Net-(U4-XI)") (class "Default")
      (node (ref "C16") (pin "2") (pinfunction "2_2") (pintype "passive"))
      (node (ref "U4") (pin "7") (pinfunction "XI_7") (pintype "passive"))
      (node (ref "Y1") (pin "2") (pinfunction "OSC2_2") (pintype "passive"))
    )
    (net (code "65") (name "Net-(U4-XO)") (class "Default")
      (node (ref "C17") (pin "2") (pinfunction "2_2") (pintype "passive"))
      (node (ref "U4") (pin "8") (pinfunction "XO_8") (pintype "passive"))
      (node (ref "Y1") (pin "1") (pinfunction "OSC1_1") (pintype "passive"))
    )
    (net (code "66") (name "VBAT") (class "Default")
      (node (ref "P5") (pin "1") (pinfunction "1_1") (pintype "passive"))
      (node (ref "R20") (pin "1") (pinfunction "1_1") (pintype "passive"))
    )
    (net (code "67") (name "VDD_SERVO") (class "Default")
      (node (ref "P1") (pin "1") (pinfunction "1_1") (pintype "passive"))
      (node (ref "P2") (pin "1") (pinfunction "1_1") (pintype "passive"))
      (node (ref "P5") (pin "2") (pinfunction "2_2") (pintype "passive"))
    )
    (net (code "68") (name "unconnected-(M1-m-Pad1)") (class "Default")
      (node (ref "M1") (pin "1") (pinfunction "m_1") (pintype "passive"))
    )
    (net (code "69") (name "unconnected-(M2-m-Pad1)") (class "Default")
      (node (ref "M2") (pin "1") (pinfunction "m_1") (pintype "passive"))
    )
    (net (code "70") (name "unconnected-(M3-m-Pad1)") (class "Default")
      (node (ref "M3") (pin "1") (pinfunction "m_1") (pintype "passive"))
    )
    (net (code "71") (name "unconnected-(M4-m-Pad1)") (class "Default")
      (node (ref "M4") (pin "1") (pinfunction "m_1") (pintype "passive"))
    )
    (net (code "72") (name "unconnected-(P5-Pad3)") (class "Default")
      (node (ref "P5") (pin "3") (pinfunction "3_3") (pintype "passive"))
    )
    (net (code "73") (name "unconnected-(U1-NC-Pad4)") (class "Default")
      (node (ref "U1") (pin "4") (pinfunction "NC_4") (pintype "passive"))
    )
    (net (code "74") (name "unconnected-(U2-NC-Pad4)") (class "Default")
      (node (ref "U2") (pin "4") (pinfunction "NC_4") (pintype "passive"))
    )
    (net (code "75") (name "unconnected-(U3-AUX_CL-Pad7)") (class "Default")
      (node (ref "U3") (pin "7") (pinfunction "AUX_CL_7") (pintype "passive"))
    )
    (net (code "76") (name "unconnected-(U3-AUX_DA-Pad6)") (class "Default")
      (node (ref "U3") (pin "6") (pinfunction "AUX_DA_6") (pintype "passive"))
    )
    (net (code "77") (name "unconnected-(U3-CLKOUT-Pad22)") (class "Default")
      (node (ref "U3") (pin "22") (pinfunction "CLKOUT_22") (pintype "passive"))
    )
    (net (code "78") (name "unconnected-(U3-INT-Pad12)") (class "Default")
      (node (ref "U3") (pin "12") (pinfunction "INT_12") (pintype "passive"))
    )
    (net (code "79") (name "unconnected-(U3-NC-Pad2)") (class "Default")
      (node (ref "U3") (pin "2") (pinfunction "NC_2") (pintype "passive"))
    )
    (net (code "80") (name "unconnected-(U3-NC-Pad3)") (class "Default")
      (node (ref "U3") (pin "3") (pinfunction "NC_3") (pintype "passive"))
    )
    (net (code "81") (name "unconnected-(U3-NC-Pad4)") (class "Default")
      (node (ref "U3") (pin "4") (pinfunction "NC_4") (pintype "passive"))
    )
    (net (code "82") (name "unconnected-(U3-NC-Pad5)") (class "Default")
      (node (ref "U3") (pin "5") (pinfunction "NC_5") (pintype "passive"))
    )
    (net (code "83") (name "unconnected-(U3-NC-Pad14)") (class "Default")
      (node (ref "U3") (pin "14") (pinfunction "NC_14") (pintype "passive"))
    )
    (net (code "84") (name "unconnected-(U3-NC-Pad15)") (class "Default")
      (node (ref "U3") (pin "15") (pinfunction "NC_15") (pintype "passive"))
    )
    (net (code "85") (name "unconnected-(U3-NC-Pad16)") (class "Default")
      (node (ref "U3") (pin "16") (pinfunction "NC_16") (pintype "passive"))
    )
    (net (code "86") (name "unconnected-(U3-NC-Pad17)") (class "Default")
      (node (ref "U3") (pin "17") (pinfunction "NC_17") (pintype "passive"))
    )
    (net (code "87") (name "unconnected-(U3-RESV-Pad19)") (class "Default")
      (node (ref "U3") (pin "19") (pinfunction "RESV_19") (pintype "passive"))
    )
    (net (code "88") (name "unconnected-(U3-RESV-Pad21)") (class "Default")
      (node (ref "U3") (pin "21") (pinfunction "RESV_21") (pintype "passive"))
    )
    (net (code "89") (name "unconnected-(U4-CTS#-Pad9)") (class "Default")
      (node (ref "U4") (pin "9") (pinfunction "CTS#_9") (pintype "passive"))
    )
    (net (code "90") (name "unconnected-(U4-DCD#-Pad12)") (class "Default")
      (node (ref "U4") (pin "12") (pinfunction "DCD#_12") (pintype "passive"))
    )
    (net (code "91") (name "unconnected-(U4-DSR#-Pad10)") (class "Default")
      (node (ref "U4") (pin "10") (pinfunction "DSR#_10") (pintype "passive"))
    )
    (net (code "92") (name "unconnected-(U4-R232-Pad15)") (class "Default")
      (node (ref "U4") (pin "15") (pinfunction "R232_15") (pintype "passive"))
    )
    (net (code "93") (name "unconnected-(U4-RI#-Pad11)") (class "Default")
      (node (ref "U4") (pin "11") (pinfunction "RI#_11") (pintype "passive"))
    )
    (net (code "94") (name "unconnected-(U5-PA0{slash}UART4_TX{slash}TIM5_CH1{slash}ADC123_IN0-Pad14)") (class "Default")
      (node (ref "U5") (pin "14") (pinfunction "PA0/UART4_TX/TIM5_CH1/ADC123_IN0_14") (pintype "bidirectional"))
    )
    (net (code "95") (name "unconnected-(U5-PA1{slash}UART4_RX{slash}TIM5_CH2{slash}TIM2_CH2{slash}ADC123_IN1-Pad15)") (class "Default")
      (node (ref "U5") (pin "15") (pinfunction "PA1/UART4_RX/TIM5_CH2/TIM2_CH2/ADC123_IN1_15") (pintype "bidirectional"))
    )
    (net (code "96") (name "unconnected-(U5-PA4{slash}SPI1_NSS{slash}SPI3_NSS{slash}ADC12_IN4{slash}DAC_OUT1-Pad20)") (class "Default")
      (node (ref "U5") (pin "20") (pinfunction "PA4/SPI1_NSS/SPI3_NSS/ADC12_IN4/DAC_OUT1_20") (pintype "bidirectional"))
    )
    (net (code "97") (name "unconnected-(U5-PA5{slash}SPI1_SCK{slash}TIM8_CH1N{slash}ADC12_IN5{slash}DAC_OUT2-Pad21)") (class "Default")
      (node (ref "U5") (pin "21") (pinfunction "PA5/SPI1_SCK/TIM8_CH1N/ADC12_IN5/DAC_OUT2_21") (pintype "bidirectional"))
    )
    (net (code "98") (name "unconnected-(U5-PA6{slash}SPI1_MISO{slash}{slash}TIM13_CH1{slash}TIM3_CH1{slash}TIM1_BKIN{slash}ADC12_IN6-Pad22)") (class "Default")
      (node (ref "U5") (pin "22") (pinfunction "PA6/SPI1_MISO//TIM13_CH1/TIM3_CH1/TIM1_BKIN/ADC12_IN6_22") (pintype "bidirectional"))
    )
    (net (code "99") (name "unconnected-(U5-PA7{slash}SPI1_MOSI{slash}TIM8_CH1N{slash}TIM14_CH1{slash}TIM3_CH2{slash}ADC12_IN14-Pad23)") (class "Default")
      (node (ref "U5") (pin "23") (pinfunction "PA7/SPI1_MOSI/TIM8_CH1N/TIM14_CH1/TIM3_CH2/ADC12_IN14_23") (pintype "bidirectional"))
    )
    (net (code "100") (name "unconnected-(U5-PA8{slash}TIM1_CH1{slash}I2C3_SCL-Pad41)") (class "Default")
      (node (ref "U5") (pin "41") (pinfunction "PA8/TIM1_CH1/I2C3_SCL_41") (pintype "bidirectional"))
    )
    (net (code "101") (name "unconnected-(U5-PA11{slash}CAN1_RX{slash}TIM1_CH4-Pad44)") (class "Default")
      (node (ref "U5") (pin "44") (pinfunction "PA11/CAN1_RX/TIM1_CH4_44") (pintype "bidirectional"))
    )
    (net (code "102") (name "unconnected-(U5-PA12{slash}CAN1_TX-Pad45)") (class "Default")
      (node (ref "U5") (pin "45") (pinfunction "PA12/CAN1_TX_45") (pintype "bidirectional"))
    )
    (net (code "103") (name "unconnected-(U5-PA15{slash}JTDI{slash}TIM2_CH1_ETR{slash}SPI1_NSS-Pad50)") (class "Default")
      (node (ref "U5") (pin "50") (pinfunction "PA15/JTDI/TIM2_CH1_ETR/SPI1_NSS_50") (pintype "bidirectional"))
    )
    (net (code "104") (name "unconnected-(U5-PB0{slash}TIM3_CH3{slash}TIM8_CH2N{slash}TIM1_CH2N{slash}ADC12_IN8-Pad26)") (class "Default")
      (node (ref "U5") (pin "26") (pinfunction "PB0/TIM3_CH3/TIM8_CH2N/TIM1_CH2N/ADC12_IN8_26") (pintype "bidirectional"))
    )
    (net (code "105") (name "unconnected-(U5-PB1{slash}TIM3_CH4{slash}TIM8_CH3N{slash}TIM1_CH3N{slash}ADC12_IN9-Pad27)") (class "Default")
      (node (ref "U5") (pin "27") (pinfunction "PB1/TIM3_CH4/TIM8_CH3N/TIM1_CH3N/ADC12_IN9_27") (pintype "bidirectional"))
    )
    (net (code "106") (name "unconnected-(U5-PB3{slash}JTDO{slash}SPI3_SCK{slash}TIM2_CH2{slash}SPI1_SCK-Pad55)") (class "Default")
      (node (ref "U5") (pin "55") (pinfunction "PB3/JTDO/SPI3_SCK/TIM2_CH2/SPI1_SCK_55") (pintype "bidirectional"))
    )
    (net (code "107") (name "unconnected-(U5-PB4{slash}NJTRES{slash}SPI3_MISO{slash}TIM3_CH1{slash}SPI1_MISO-Pad56)") (class "Default")
      (node (ref "U5") (pin "56") (pinfunction "PB4/NJTRES/SPI3_MISO/TIM3_CH1/SPI1_MISO_56") (pintype "bidirectional"))
    )
    (net (code "108") (name "unconnected-(U5-PB5{slash}CAN2_RX{slash}TIM3_CH2{slash}SPI1_MOSI{slash}SPI3_MOSI-Pad57)") (class "Default")
      (node (ref "U5") (pin "57") (pinfunction "PB5/CAN2_RX/TIM3_CH2/SPI1_MOSI/SPI3_MOSI_57") (pintype "bidirectional"))
    )
    (net (code "109") (name "unconnected-(U5-PC2{slash}SPI2_MISO{slash}ADC123_IN12-Pad10)") (class "Default")
      (node (ref "U5") (pin "10") (pinfunction "PC2/SPI2_MISO/ADC123_IN12_10") (pintype "bidirectional"))
    )
    (net (code "110") (name "unconnected-(U5-PC3{slash}SPI2_MOSI{slash}ADC123_IN13-Pad11)") (class "Default")
      (node (ref "U5") (pin "11") (pinfunction "PC3/SPI2_MOSI/ADC123_IN13_11") (pintype "bidirectional"))
    )
    (net (code "111") (name "unconnected-(U5-PC4{slash}ADC12_IN14-Pad24)") (class "Default")
      (node (ref "U5") (pin "24") (pinfunction "PC4/ADC12_IN14_24") (pintype "bidirectional"))
    )
    (net (code "112") (name "unconnected-(U5-PC12{slash}UART5_TX{slash}SPI3_MOSI-Pad53)") (class "Default")
      (node (ref "U5") (pin "53") (pinfunction "PC12/UART5_TX/SPI3_MOSI_53") (pintype "bidirectional"))
    )
    (net (code "113") (name "unconnected-(U5-PC13{slash}RTC_OUT{slash}RTC_TAMP1{slash}RTC_TS-Pad2)") (class "Default")
      (node (ref "U5") (pin "2") (pinfunction "PC13/RTC_OUT/RTC_TAMP1/RTC_TS_2") (pintype "bidirectional"))
    )
    (net (code "114") (name "unconnected-(U5-PC14{slash}OSC32_IN-Pad3)") (class "Default")
      (node (ref "U5") (pin "3") (pinfunction "PC14/OSC32_IN_3") (pintype "bidirectional"))
    )
    (net (code "115") (name "unconnected-(U5-PC15{slash}OSC32_OUT-Pad4)") (class "Default")
      (node (ref "U5") (pin "4") (pinfunction "PC15/OSC32_OUT_4") (pintype "bidirectional"))
    )
    (net (code "116") (name "unconnected-(U5-PD2{slash}TIM3_ETR{slash}UART5_RX-Pad54)") (class "Default")
      (node (ref "U5") (pin "54") (pinfunction "PD2/TIM3_ETR/UART5_RX_54") (pintype "bidirectional"))
    )
  )
)
